# Encoders.net
KiCad netlist of a schematic drawn in Altium Designer
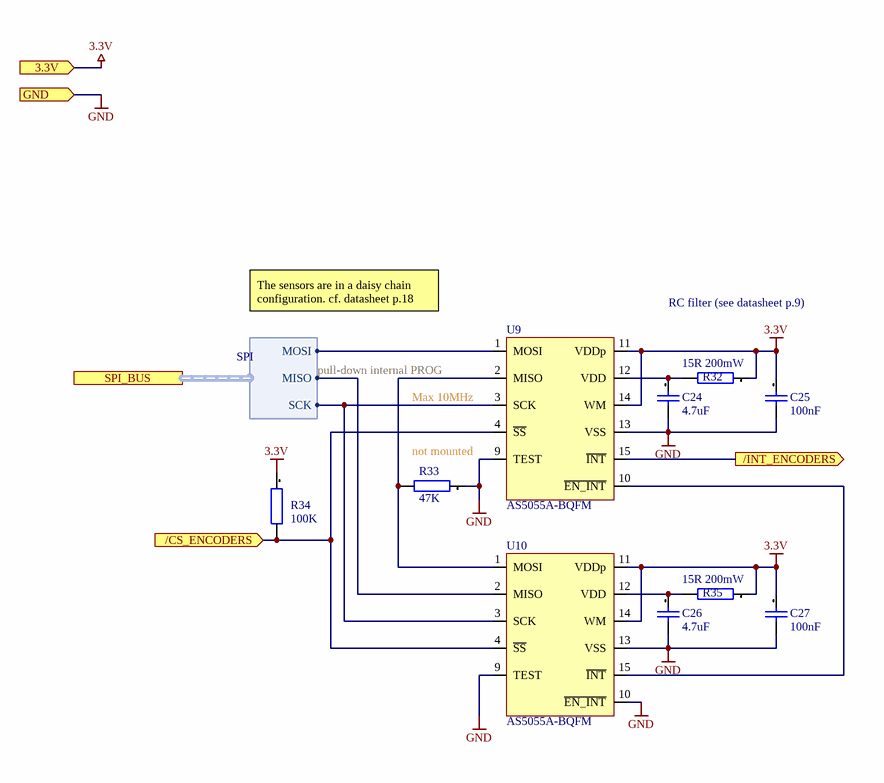
[diagram p0: Encoders.SchDoc]

(export (version "E")
  (design (tool "Eeschema 10.0.6"))
  (components
    (comp (ref "C24")
      (value "4.7uF")
      (footprint "CAPC1608X08L")
      (description "Capacitor TBD 0603")
      (libsource (lib "LSRO1Altium") (part "CAP-NP"))
    )
    (comp (ref "C25")
      (value "100nF")
      (footprint "CAPC1608X08L")
      (description "Capacitor TBD 0603")
      (libsource (lib "LSRO1Altium") (part "CAP-NP"))
    )
    (comp (ref "C26")
      (value "4.7uF")
      (footprint "CAPC1608X08L")
      (description "Capacitor TBD 0603")
      (libsource (lib "LSRO1Altium") (part "CAP-NP"))
    )
    (comp (ref "C27")
      (value "100nF")
      (footprint "CAPC1608X08L")
      (description "Capacitor TBD 0603")
      (libsource (lib "LSRO1Altium") (part "CAP-NP"))
    )
    (comp (ref "R32")
      (value "15R 200mW")
      (footprint "RESC1608X06N")
      (description "Resistor ToDo 0603")
      (libsource (lib "LSRO1Altium") (part "RES"))
    )
    (comp (ref "R33")
      (value "47K")
      (footprint "RESC1608X06N")
      (description "Resistor ToDo 0603")
      (libsource (lib "LSRO1Altium") (part "RES"))
    )
    (comp (ref "R34")
      (value "100K")
      (footprint "RESC1608X06N")
      (description "Resistor ToDo 0603")
      (libsource (lib "LSRO1Altium") (part "RES"))
    )
    (comp (ref "R35")
      (value "15R 200mW")
      (footprint "RESC1608X06N")
      (description "Resistor ToDo 0603")
      (libsource (lib "LSRO1Altium") (part "RES"))
    )
    (comp (ref "U9")
      (value "AS5055A-BQFM")
      (footprint "QFN4X4-16 - EPAD unconnected")
      (description "IC ENCODER ROTARY 12BIT 16QFN")
      (fields (field (name "MANUFACTURER") "ams"))
      (libsource (lib "Schlib") (part "AS5055A-BQFM"))
    )
    (comp (ref "U10")
      (value "AS5055A-BQFM")
      (footprint "QFN4X4-16 - EPAD unconnected")
      (description "IC ENCODER ROTARY 12BIT 16QFN")
      (fields (field (name "MANUFACTURER") "ams"))
      (libsource (lib "Schlib") (part "AS5055A-BQFM"))
    )
  )
  (nets
    (net (code "2") (name "/MISO") (class "Default")
      (node (ref "U10") (pin "2") (pinfunction "MISO_2") (pintype "passive"))
    )
    (net (code "3") (name "/MOSI") (class "Default")
      (node (ref "U9") (pin "1") (pinfunction "MOSI_1") (pintype "passive"))
    )
    (net (code "4") (name "/SCK") (class "Default")
      (node (ref "U10") (pin "3") (pinfunction "SCK_3") (pintype "passive"))
      (node (ref "U9") (pin "3") (pinfunction "SCK_3") (pintype "passive"))
    )
    (net (code "6") (name "/{slash}CS_ENCODERS") (class "Default")
      (node (ref "R34") (pin "2") (pinfunction "2_2") (pintype "passive"))
      (node (ref "U10") (pin "4") (pinfunction "~{SS}_4") (pintype "passive"))
      (node (ref "U9") (pin "4") (pinfunction "~{SS}_4") (pintype "passive"))
    )
    (net (code "7") (name "/{slash}INT_ENCODERS") (class "Default")
      (node (ref "U9") (pin "15") (pinfunction "~{INT}_15") (pintype "passive"))
    )
    (net (code "8") (name "3.3V") (class "Default")
      (node (ref "C25") (pin "1") (pinfunction "1_1") (pintype "passive"))
      (node (ref "C27") (pin "1") (pinfunction "1_1") (pintype "passive"))
      (node (ref "R32") (pin "1") (pinfunction "1_1") (pintype "passive"))
      (node (ref "R34") (pin "1") (pinfunction "1_1") (pintype "passive"))
      (node (ref "R35") (pin "1") (pinfunction "1_1") (pintype "passive"))
      (node (ref "U10") (pin "11") (pinfunction "VDDp_11") (pintype "passive"))
      (node (ref "U10") (pin "14") (pinfunction "WM_14") (pintype "passive"))
      (node (ref "U9") (pin "11") (pinfunction "VDDp_11") (pintype "passive"))
      (node (ref "U9") (pin "14") (pinfunction "WM_14") (pintype "passive"))
    )
    (net (code "9") (name "GND") (class "Default")
      (node (ref "C24") (pin "2") (pinfunction "2_2") (pintype "passive"))
      (node (ref "C25") (pin "2") (pinfunction "2_2") (pintype "passive"))
      (node (ref "C26") (pin "2") (pinfunction "2_2") (pintype "passive"))
      (node (ref "C27") (pin "2") (pinfunction "2_2") (pintype "passive"))
      (node (ref "R33") (pin "1") (pinfunction "1_1") (pintype "passive"))
      (node (ref "U10") (pin "10") (pinfunction "~{EN_INT}_10") (pintype "passive"))
      (node (ref "U10") (pin "13") (pinfunction "VSS_13") (pintype "passive"))
      (node (ref "U10") (pin "9") (pinfunction "TEST_9") (pintype "passive"))
      (node (ref "U9") (pin "13") (pinfunction "VSS_13") (pintype "passive"))
      (node (ref "U9") (pin "9") (pinfunction "TEST_9") (pintype "passive"))
    )
    (net (code "10") (name "Net-(U9-VDD)") (class "Default")
      (node (ref "C24") (pin "1") (pinfunction "1_1") (pintype "passive"))
      (node (ref "R32") (pin "2") (pinfunction "2_2") (pintype "passive"))
      (node (ref "U9") (pin "12") (pinfunction "VDD_12") (pintype "passive"))
    )
    (net (code "11") (name "Net-(U10-MOSI)") (class "Default")
      (node (ref "R33") (pin "2") (pinfunction "2_2") (pintype "passive"))
      (node (ref "U10") (pin "1") (pinfunction "MOSI_1") (pintype "passive"))
      (node (ref "U9") (pin "2") (pinfunction "MISO_2") (pintype "passive"))
    )
    (net (code "12") (name "Net-(U10-VDD)") (class "Default")
      (node (ref "C26") (pin "1") (pinfunction "1_1") (pintype "passive"))
      (node (ref "R35") (pin "2") (pinfunction "2_2") (pintype "passive"))
      (node (ref "U10") (pin "12") (pinfunction "VDD_12") (pintype "passive"))
    )
    (net (code "13") (name "Net-(U10-~{INT})") (class "Default")
      (node (ref "U10") (pin "15") (pinfunction "~{INT}_15") (pintype "passive"))
      (node (ref "U9") (pin "10") (pinfunction "~{EN_INT}_10") (pintype "passive"))
    )
  )
)
